# sch.net
KiCad netlist of a schematic drawn in EAGLE
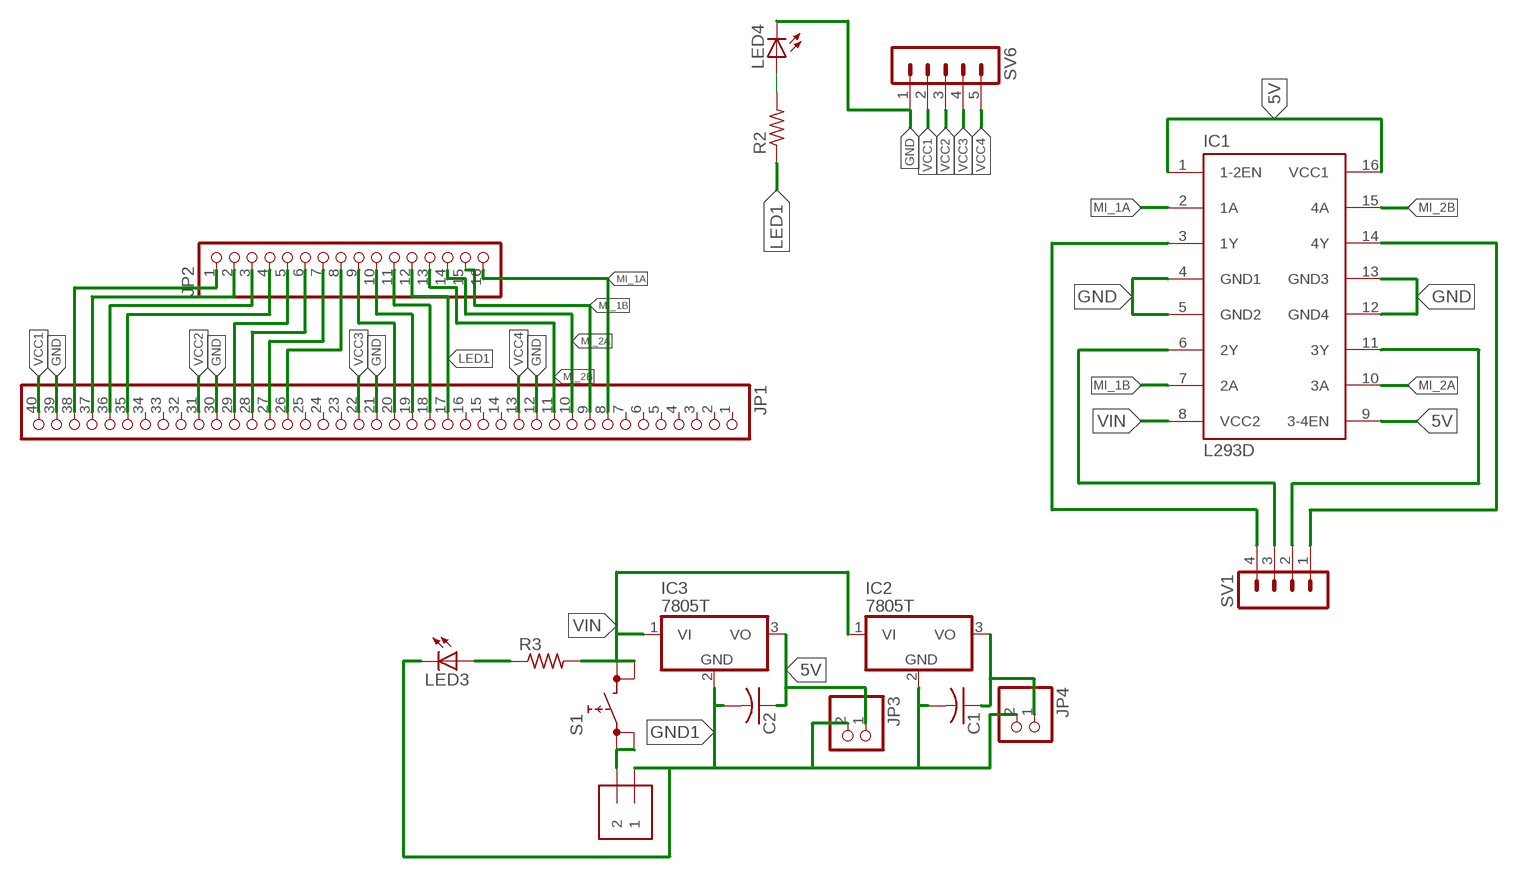
[diagram p0: schematic, sheet 1]

(export (version "E")
  (design (tool "Eeschema 10.0.6"))
  (components
    (comp (ref "C1")
      (value "C-US025-024X044")
      (footprint "eagle-import:C025-024X044")
      (libsource (lib "eagle-import") (part "C-US025-024X044"))
    )
    (comp (ref "C2")
      (value "C-US025-024X044")
      (footprint "eagle-import:C025-024X044")
      (libsource (lib "eagle-import") (part "C-US025-024X044"))
    )
    (comp (ref "IC1")
      (value "L293D")
      (footprint "eagle-import:DIL16")
      (libsource (lib "eagle-import") (part "L293D"))
    )
    (comp (ref "IC2")
      (value "7805T")
      (footprint "eagle-import:TO220H")
      (libsource (lib "eagle-import") (part "78T05"))
    )
    (comp (ref "IC3")
      (value "7805T")
      (footprint "eagle-import:TO220H")
      (libsource (lib "eagle-import") (part "78T05"))
    )
    (comp (ref "J1")
      (value "1X2-3.5MM")
      (footprint "eagle-import:1X2-3.5MM")
      (libsource (lib "eagle-import") (part "1X2-3.5MM"))
    )
    (comp (ref "JP1")
      (value "PINHD-1X40")
      (footprint "eagle-import:1X40")
      (libsource (lib "eagle-import") (part "PINHD-1X40"))
    )
    (comp (ref "JP2")
      (value "PINHD-1X16")
      (footprint "eagle-import:1X16")
      (libsource (lib "eagle-import") (part "PINHD-1X16"))
    )
    (comp (ref "JP3")
      (value "PINHD-1X2")
      (footprint "eagle-import:1X02")
      (libsource (lib "eagle-import") (part "PINHD-1X2"))
    )
    (comp (ref "JP4")
      (value "PINHD-1X2")
      (footprint "eagle-import:1X02")
      (libsource (lib "eagle-import") (part "PINHD-1X2"))
    )
    (comp (ref "LED3")
      (value "LED5MM")
      (footprint "eagle-import:LED5MM")
      (libsource (lib "eagle-import") (part "LED5MM"))
    )
    (comp (ref "LED4")
      (value "LED5MM")
      (footprint "eagle-import:LED5MM")
      (libsource (lib "eagle-import") (part "LED5MM"))
    )
    (comp (ref "R2")
      (value "R-US_0204/2V")
      (footprint "eagle-import:0204V")
      (libsource (lib "eagle-import") (part "R-US_0204/2V"))
    )
    (comp (ref "R3")
      (value "R-US_0204/2V")
      (footprint "eagle-import:0204V")
      (libsource (lib "eagle-import") (part "R-US_0204/2V"))
    )
    (comp (ref "S1")
      (value "REKN")
      (footprint "eagle-import:REKN")
      (libsource (lib "eagle-import") (part "REKN"))
    )
    (comp (ref "SV1")
      (value "MA04-1")
      (footprint "eagle-import:MA04-1")
      (libsource (lib "eagle-import") (part "MA04-1"))
    )
    (comp (ref "SV6")
      (value "MA05-1")
      (footprint "eagle-import:MA05-1")
      (libsource (lib "eagle-import") (part "MA05-1"))
    )
  )
  (nets
    (net (code "1") (name "5V") (class "Default")
      (node (ref "C2") (pin "1") (pinfunction "1_1") (pintype "passive"))
      (node (ref "IC1") (pin "1") (pinfunction "1-2EN_1") (pintype "input"))
      (node (ref "IC1") (pin "16") (pinfunction "VCC1_16") (pintype "power_in"))
      (node (ref "IC1") (pin "9") (pinfunction "3-4EN_9") (pintype "input"))
      (node (ref "IC3") (pin "3") (pinfunction "VO_3") (pintype "passive"))
      (node (ref "JP3") (pin "1") (pinfunction "1_1") (pintype "passive"))
    )
    (net (code "2") (name "GND") (class "Default")
      (node (ref "IC1") (pin "12") (pinfunction "GND4_12") (pintype "power_in"))
      (node (ref "IC1") (pin "13") (pinfunction "GND3_13") (pintype "power_in"))
      (node (ref "IC1") (pin "4") (pinfunction "GND1_4") (pintype "power_in"))
      (node (ref "IC1") (pin "5") (pinfunction "GND2_5") (pintype "power_in"))
      (node (ref "JP1") (pin "12") (pinfunction "12_12") (pintype "passive"))
      (node (ref "JP1") (pin "21") (pinfunction "21_21") (pintype "passive"))
      (node (ref "JP1") (pin "30") (pinfunction "30_30") (pintype "passive"))
      (node (ref "JP1") (pin "39") (pinfunction "39_39") (pintype "passive"))
      (node (ref "LED4") (pin "K") (pinfunction "C_K") (pintype "passive"))
      (node (ref "SV6") (pin "1") (pinfunction "1_1") (pintype "passive"))
    )
    (net (code "3") (name "GND1") (class "Default")
      (node (ref "C1") (pin "2") (pinfunction "2_2") (pintype "passive"))
      (node (ref "C2") (pin "2") (pinfunction "2_2") (pintype "passive"))
      (node (ref "IC2") (pin "2") (pinfunction "GND_2") (pintype "passive"))
      (node (ref "IC3") (pin "2") (pinfunction "GND_2") (pintype "passive"))
      (node (ref "J1") (pin "1") (pinfunction "1_1") (pintype "passive"))
      (node (ref "JP3") (pin "2") (pinfunction "2_2") (pintype "passive"))
      (node (ref "JP4") (pin "2") (pinfunction "2_2") (pintype "passive"))
      (node (ref "LED3") (pin "K") (pinfunction "C_K") (pintype "passive"))
    )
    (net (code "4") (name "LED1") (class "Default")
      (node (ref "JP1") (pin "17") (pinfunction "17_17") (pintype "passive"))
      (node (ref "JP2") (pin "12") (pinfunction "12_12") (pintype "passive"))
      (node (ref "R2") (pin "1") (pinfunction "1_1") (pintype "passive"))
    )
    (net (code "5") (name "MI_1A") (class "Default")
      (node (ref "IC1") (pin "2") (pinfunction "1A_2") (pintype "input"))
      (node (ref "JP1") (pin "8") (pinfunction "8_8") (pintype "passive"))
      (node (ref "JP2") (pin "16") (pinfunction "16_16") (pintype "passive"))
    )
    (net (code "6") (name "MI_1B") (class "Default")
      (node (ref "IC1") (pin "7") (pinfunction "2A_7") (pintype "input"))
      (node (ref "JP1") (pin "9") (pinfunction "9_9") (pintype "passive"))
      (node (ref "JP2") (pin "15") (pinfunction "15_15") (pintype "passive"))
    )
    (net (code "7") (name "MI_2A") (class "Default")
      (node (ref "IC1") (pin "10") (pinfunction "3A_10") (pintype "input"))
      (node (ref "JP1") (pin "10") (pinfunction "10_10") (pintype "passive"))
      (node (ref "JP2") (pin "14") (pinfunction "14_14") (pintype "passive"))
    )
    (net (code "8") (name "MI_2B") (class "Default")
      (node (ref "IC1") (pin "15") (pinfunction "4A_15") (pintype "input"))
      (node (ref "JP1") (pin "11") (pinfunction "11_11") (pintype "passive"))
      (node (ref "JP2") (pin "13") (pinfunction "13_13") (pintype "passive"))
    )
    (net (code "9") (name "Net-(IC1-1Y)") (class "Default")
      (node (ref "IC1") (pin "3") (pinfunction "1Y_3") (pintype "output"))
      (node (ref "SV1") (pin "4") (pinfunction "4_4") (pintype "passive"))
    )
    (net (code "10") (name "Net-(IC1-2Y)") (class "Default")
      (node (ref "IC1") (pin "6") (pinfunction "2Y_6") (pintype "output"))
      (node (ref "SV1") (pin "3") (pinfunction "3_3") (pintype "passive"))
    )
    (net (code "11") (name "Net-(IC1-3Y)") (class "Default")
      (node (ref "IC1") (pin "11") (pinfunction "3Y_11") (pintype "output"))
      (node (ref "SV1") (pin "2") (pinfunction "2_2") (pintype "passive"))
    )
    (net (code "12") (name "Net-(IC1-4Y)") (class "Default")
      (node (ref "IC1") (pin "14") (pinfunction "4Y_14") (pintype "output"))
      (node (ref "SV1") (pin "1") (pinfunction "1_1") (pintype "passive"))
    )
    (net (code "13") (name "Net-(IC2-VO)") (class "Default")
      (node (ref "C1") (pin "1") (pinfunction "1_1") (pintype "passive"))
      (node (ref "IC2") (pin "3") (pinfunction "VO_3") (pintype "passive"))
      (node (ref "JP4") (pin "1") (pinfunction "1_1") (pintype "passive"))
    )
    (net (code "14") (name "Net-(J1-Pad2)") (class "Default")
      (node (ref "J1") (pin "2") (pinfunction "2_2") (pintype "passive"))
      (node (ref "S1") (pin "0A") (pinfunction "0_0A") (pintype "passive"))
      (node (ref "S1") (pin "0B") (pinfunction "0_0B") (pintype "passive"))
    )
    (net (code "15") (name "Net-(JP1-Pad18)") (class "Default")
      (node (ref "JP1") (pin "18") (pinfunction "18_18") (pintype "passive"))
      (node (ref "JP2") (pin "11") (pinfunction "11_11") (pintype "passive"))
    )
    (net (code "16") (name "Net-(JP1-Pad19)") (class "Default")
      (node (ref "JP1") (pin "19") (pinfunction "19_19") (pintype "passive"))
      (node (ref "JP2") (pin "10") (pinfunction "10_10") (pintype "passive"))
    )
    (net (code "17") (name "Net-(JP1-Pad20)") (class "Default")
      (node (ref "JP1") (pin "20") (pinfunction "20_20") (pintype "passive"))
      (node (ref "JP2") (pin "9") (pinfunction "9_9") (pintype "passive"))
    )
    (net (code "18") (name "Net-(JP1-Pad26)") (class "Default")
      (node (ref "JP1") (pin "26") (pinfunction "26_26") (pintype "passive"))
      (node (ref "JP2") (pin "8") (pinfunction "8_8") (pintype "passive"))
    )
    (net (code "19") (name "Net-(JP1-Pad27)") (class "Default")
      (node (ref "JP1") (pin "27") (pinfunction "27_27") (pintype "passive"))
      (node (ref "JP2") (pin "7") (pinfunction "7_7") (pintype "passive"))
    )
    (net (code "20") (name "Net-(JP1-Pad28)") (class "Default")
      (node (ref "JP1") (pin "28") (pinfunction "28_28") (pintype "passive"))
      (node (ref "JP2") (pin "6") (pinfunction "6_6") (pintype "passive"))
    )
    (net (code "21") (name "Net-(JP1-Pad29)") (class "Default")
      (node (ref "JP1") (pin "29") (pinfunction "29_29") (pintype "passive"))
      (node (ref "JP2") (pin "5") (pinfunction "5_5") (pintype "passive"))
    )
    (net (code "22") (name "Net-(JP1-Pad35)") (class "Default")
      (node (ref "JP1") (pin "35") (pinfunction "35_35") (pintype "passive"))
      (node (ref "JP2") (pin "4") (pinfunction "4_4") (pintype "passive"))
    )
    (net (code "23") (name "Net-(JP1-Pad36)") (class "Default")
      (node (ref "JP1") (pin "36") (pinfunction "36_36") (pintype "passive"))
      (node (ref "JP2") (pin "3") (pinfunction "3_3") (pintype "passive"))
    )
    (net (code "24") (name "Net-(JP1-Pad37)") (class "Default")
      (node (ref "JP1") (pin "37") (pinfunction "37_37") (pintype "passive"))
      (node (ref "JP2") (pin "2") (pinfunction "2_2") (pintype "passive"))
    )
    (net (code "25") (name "Net-(JP1-Pad38)") (class "Default")
      (node (ref "JP1") (pin "38") (pinfunction "38_38") (pintype "passive"))
      (node (ref "JP2") (pin "1") (pinfunction "1_1") (pintype "passive"))
    )
    (net (code "26") (name "Net-(LED3-PadA)") (class "Default")
      (node (ref "LED3") (pin "A") (pinfunction "A_A") (pintype "passive"))
      (node (ref "R3") (pin "1") (pinfunction "1_1") (pintype "passive"))
    )
    (net (code "27") (name "Net-(LED4-PadA)") (class "Default")
      (node (ref "LED4") (pin "A") (pinfunction "A_A") (pintype "passive"))
      (node (ref "R2") (pin "2") (pinfunction "2_2") (pintype "passive"))
    )
    (net (code "28") (name "VCC1") (class "Default")
      (node (ref "JP1") (pin "40") (pinfunction "40_40") (pintype "passive"))
      (node (ref "SV6") (pin "2") (pinfunction "2_2") (pintype "passive"))
    )
    (net (code "29") (name "VCC2") (class "Default")
      (node (ref "JP1") (pin "31") (pinfunction "31_31") (pintype "passive"))
      (node (ref "SV6") (pin "3") (pinfunction "3_3") (pintype "passive"))
    )
    (net (code "30") (name "VCC3") (class "Default")
      (node (ref "JP1") (pin "22") (pinfunction "22_22") (pintype "passive"))
      (node (ref "SV6") (pin "4") (pinfunction "4_4") (pintype "passive"))
    )
    (net (code "31") (name "VCC4") (class "Default")
      (node (ref "JP1") (pin "13") (pinfunction "13_13") (pintype "passive"))
      (node (ref "SV6") (pin "5") (pinfunction "5_5") (pintype "passive"))
    )
    (net (code "32") (name "VIN") (class "Default")
      (node (ref "IC1") (pin "8") (pinfunction "VCC2_8") (pintype "power_in"))
      (node (ref "IC2") (pin "1") (pinfunction "VI_1") (pintype "input"))
      (node (ref "IC3") (pin "1") (pinfunction "VI_1") (pintype "input"))
      (node (ref "R3") (pin "2") (pinfunction "2_2") (pintype "passive"))
      (node (ref "S1") (pin "1A") (pinfunction "1_1A") (pintype "passive"))
      (node (ref "S1") (pin "1B") (pinfunction "1_1B") (pintype "passive"))
    )
    (net (code "33") (name "unconnected-(JP1-Pad1)") (class "Default")
      (node (ref "JP1") (pin "1") (pinfunction "1_1") (pintype "passive"))
    )
    (net (code "34") (name "unconnected-(JP1-Pad2)") (class "Default")
      (node (ref "JP1") (pin "2") (pinfunction "2_2") (pintype "passive"))
    )
    (net (code "35") (name "unconnected-(JP1-Pad3)") (class "Default")
      (node (ref "JP1") (pin "3") (pinfunction "3_3") (pintype "passive"))
    )
    (net (code "36") (name "unconnected-(JP1-Pad4)") (class "Default")
      (node (ref "JP1") (pin "4") (pinfunction "4_4") (pintype "passive"))
    )
    (net (code "37") (name "unconnected-(JP1-Pad5)") (class "Default")
      (node (ref "JP1") (pin "5") (pinfunction "5_5") (pintype "passive"))
    )
    (net (code "38") (name "unconnected-(JP1-Pad6)") (class "Default")
      (node (ref "JP1") (pin "6") (pinfunction "6_6") (pintype "passive"))
    )
    (net (code "39") (name "unconnected-(JP1-Pad7)") (class "Default")
      (node (ref "JP1") (pin "7") (pinfunction "7_7") (pintype "passive"))
    )
    (net (code "40") (name "unconnected-(JP1-Pad14)") (class "Default")
      (node (ref "JP1") (pin "14") (pinfunction "14_14") (pintype "passive"))
    )
    (net (code "41") (name "unconnected-(JP1-Pad15)") (class "Default")
      (node (ref "JP1") (pin "15") (pinfunction "15_15") (pintype "passive"))
    )
    (net (code "42") (name "unconnected-(JP1-Pad16)") (class "Default")
      (node (ref "JP1") (pin "16") (pinfunction "16_16") (pintype "passive"))
    )
    (net (code "43") (name "unconnected-(JP1-Pad23)") (class "Default")
      (node (ref "JP1") (pin "23") (pinfunction "23_23") (pintype "passive"))
    )
    (net (code "44") (name "unconnected-(JP1-Pad24)") (class "Default")
      (node (ref "JP1") (pin "24") (pinfunction "24_24") (pintype "passive"))
    )
    (net (code "45") (name "unconnected-(JP1-Pad25)") (class "Default")
      (node (ref "JP1") (pin "25") (pinfunction "25_25") (pintype "passive"))
    )
    (net (code "46") (name "unconnected-(JP1-Pad32)") (class "Default")
      (node (ref "JP1") (pin "32") (pinfunction "32_32") (pintype "passive"))
    )
    (net (code "47") (name "unconnected-(JP1-Pad33)") (class "Default")
      (node (ref "JP1") (pin "33") (pinfunction "33_33") (pintype "passive"))
    )
    (net (code "48") (name "unconnected-(JP1-Pad34)") (class "Default")
      (node (ref "JP1") (pin "34") (pinfunction "34_34") (pintype "passive"))
    )
  )
)
